# Geniric_220VAC_24VDC_cup_wash.net
KiCad netlist of a schematic drawn in EAGLE
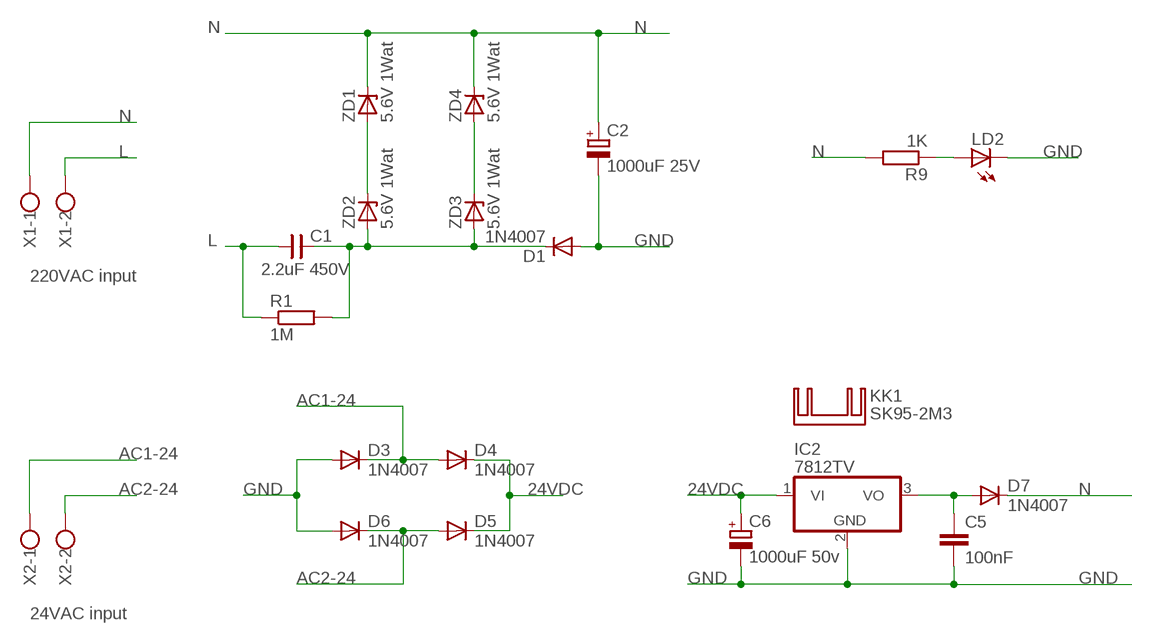
[diagram p0: schematic, sheet 1]
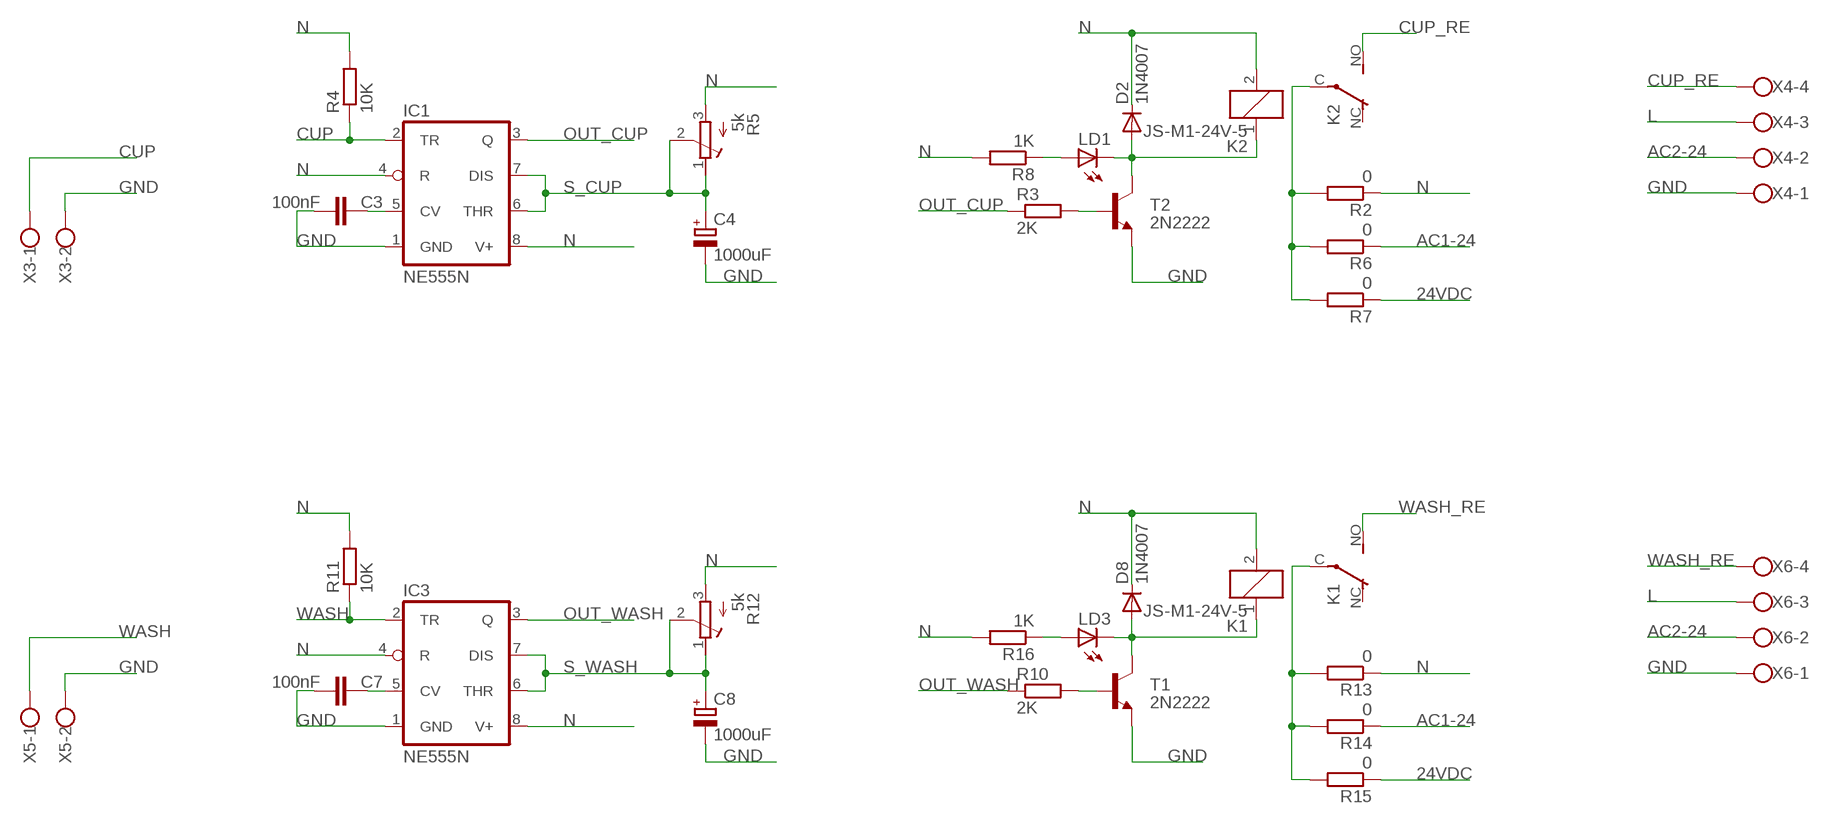
[diagram p1: schematic, sheet 2]

(export (version "E")
  (design (tool "Eeschema 10.0.6"))
  (components
    (comp (ref "C1")
      (value "2.2uF 450V")
      (footprint "eagle-import:C150-190X070")
      (libsource (lib "eagle-import") (part "CNP-C150-190X070"))
    )
    (comp (ref "C2")
      (value "1000uF 25V")
      (footprint "eagle-import:E5-8,5")
      (libsource (lib "eagle-import") (part "CPOL-EUE5-8.5"))
    )
    (comp (ref "C5")
      (value "100nF")
      (footprint "eagle-import:C050-025X075")
      (libsource (lib "eagle-import") (part "C-EU050-025X075"))
    )
    (comp (ref "C6")
      (value "1000uF 50v")
      (footprint "eagle-import:E5-13")
      (libsource (lib "eagle-import") (part "CPOL-EUE5-13"))
    )
    (comp (ref "D1")
      (value "1N4007")
      (footprint "eagle-import:DO41-10")
      (libsource (lib "eagle-import") (part "1N4004"))
    )
    (comp (ref "D3")
      (value "1N4007")
      (footprint "eagle-import:DO41-10")
      (libsource (lib "eagle-import") (part "adafruit_420_1N4004"))
    )
    (comp (ref "D4")
      (value "1N4007")
      (footprint "eagle-import:DO41-10")
      (libsource (lib "eagle-import") (part "adafruit_420_1N4004"))
    )
    (comp (ref "D5")
      (value "1N4007")
      (footprint "eagle-import:DO41-10")
      (libsource (lib "eagle-import") (part "adafruit_420_1N4004"))
    )
    (comp (ref "D6")
      (value "1N4007")
      (footprint "eagle-import:DO41-10")
      (libsource (lib "eagle-import") (part "adafruit_420_1N4004"))
    )
    (comp (ref "D7")
      (value "1N4007")
      (footprint "eagle-import:DO41-10")
      (libsource (lib "eagle-import") (part "adafruit_420_1N4004"))
    )
    (comp (ref "IC2")
      (value "7812TV")
      (footprint "eagle-import:TO220V")
      (libsource (lib "eagle-import") (part "78TV12"))
    )
    (comp (ref "KK1")
      (value "SK95-2M3")
      (footprint "eagle-import:SK95-2M3")
      (libsource (lib "eagle-import") (part "SK95-2M3"))
    )
    (comp (ref "LD2")
      (value "LED5MM")
      (footprint "eagle-import:LED5MM")
      (libsource (lib "eagle-import") (part "LED5MM"))
    )
    (comp (ref "R1")
      (value "1M")
      (footprint "eagle-import:0207_10")
      (libsource (lib "eagle-import") (part "rcl_334_R-EU_0207/10"))
    )
    (comp (ref "R9")
      (value "1K")
      (footprint "eagle-import:0207_10")
      (libsource (lib "eagle-import") (part "R-EU_0207/10"))
    )
    (comp (ref "X1")
      (value "W237-102")
      (footprint "eagle-import:W237-102")
      (libsource (lib "eagle-import") (part "W237-102"))
    )
    (comp (ref "X2")
      (value "W237-102")
      (footprint "eagle-import:W237-102")
      (libsource (lib "eagle-import") (part "W237-102"))
    )
    (comp (ref "ZD1")
      (value "5.6V 1Wat")
      (footprint "eagle-import:DO35Z10")
      (libsource (lib "eagle-import") (part "ZD-DO35Z10"))
    )
    (comp (ref "ZD2")
      (value "5.6V 1Wat")
      (footprint "eagle-import:DO35Z10")
      (libsource (lib "eagle-import") (part "ZD-DO35Z10"))
    )
    (comp (ref "ZD3")
      (value "5.6V 1Wat")
      (footprint "eagle-import:DO35Z10")
      (libsource (lib "eagle-import") (part "ZD-DO35Z10"))
    )
    (comp (ref "ZD4")
      (value "5.6V 1Wat")
      (footprint "eagle-import:DO35Z10")
      (libsource (lib "eagle-import") (part "ZD-DO35Z10"))
    )
    (comp (ref "C3")
      (value "100nF")
      (footprint "eagle-import:C050-025X075")
      (libsource (lib "eagle-import") (part "C-EU050-025X075"))
    )
    (comp (ref "C4")
      (value "1000uF")
      (footprint "eagle-import:E5-8,5")
      (libsource (lib "eagle-import") (part "CPOL-EUE5-8.5"))
    )
    (comp (ref "C7")
      (value "100nF")
      (footprint "eagle-import:C050-025X075")
      (libsource (lib "eagle-import") (part "C-EU050-025X075"))
    )
    (comp (ref "C8")
      (value "1000uF")
      (footprint "eagle-import:E5-8,5")
      (libsource (lib "eagle-import") (part "CPOL-EUE5-8.5"))
    )
    (comp (ref "D2")
      (value "1N4007")
      (footprint "eagle-import:DO41-10")
      (libsource (lib "eagle-import") (part "1N4004"))
    )
    (comp (ref "D8")
      (value "1N4007")
      (footprint "eagle-import:DO41-10")
      (libsource (lib "eagle-import") (part "1N4004"))
    )
    (comp (ref "IC1")
      (value "NE555N")
      (footprint "eagle-import:DIL08-ROUND")
      (libsource (lib "eagle-import") (part "555NNE"))
    )
    (comp (ref "IC3")
      (value "NE555N")
      (footprint "eagle-import:DIL08-ROUND")
      (libsource (lib "eagle-import") (part "555NNE"))
    )
    (comp (ref "K1")
      (value "JS-M1-24V-5")
      (footprint "eagle-import:JS-M")
      (fields (field (name "MF") "FARNELL") (field (name "MPN") "JSM1-12V-5"))
      (libsource (lib "eagle-import") (part "JS-M1-12V-5"))
    )
    (comp (ref "K2")
      (value "JS-M1-24V-5")
      (footprint "eagle-import:JS-M")
      (fields (field (name "MF") "FARNELL") (field (name "MPN") "JSM1-12V-5"))
      (libsource (lib "eagle-import") (part "JS-M1-12V-5"))
    )
    (comp (ref "LD1")
      (value "LED5MM")
      (footprint "eagle-import:LED5MM")
      (libsource (lib "eagle-import") (part "LED5MM"))
    )
    (comp (ref "LD3")
      (value "LED5MM")
      (footprint "eagle-import:LED5MM")
      (libsource (lib "eagle-import") (part "LED5MM"))
    )
    (comp (ref "R2")
      (value "0")
      (footprint "eagle-import:0207_10")
      (libsource (lib "eagle-import") (part "R-EU_0207/10"))
    )
    (comp (ref "R3")
      (value "2K")
      (footprint "eagle-import:0207_10")
      (libsource (lib "eagle-import") (part "R-EU_0207/10"))
    )
    (comp (ref "R4")
      (value "10K")
      (footprint "eagle-import:0207_10")
      (libsource (lib "eagle-import") (part "R-EU_0207/10"))
    )
    (comp (ref "R5")
      (value "5k")
      (footprint "eagle-import:RTRIMT93XA")
      (libsource (lib "eagle-import") (part "R-TRIMMT93XA"))
    )
    (comp (ref "R6")
      (value "0")
      (footprint "eagle-import:0207_10")
      (libsource (lib "eagle-import") (part "R-EU_0207/10"))
    )
    (comp (ref "R7")
      (value "0")
      (footprint "eagle-import:0207_10")
      (libsource (lib "eagle-import") (part "R-EU_0207/10"))
    )
    (comp (ref "R8")
      (value "1K")
      (footprint "eagle-import:0207_10")
      (libsource (lib "eagle-import") (part "R-EU_0207/10"))
    )
    (comp (ref "R10")
      (value "2K")
      (footprint "eagle-import:0207_10")
      (libsource (lib "eagle-import") (part "R-EU_0207/10"))
    )
    (comp (ref "R11")
      (value "10K")
      (footprint "eagle-import:0207_10")
      (libsource (lib "eagle-import") (part "R-EU_0207/10"))
    )
    (comp (ref "R12")
      (value "5k")
      (footprint "eagle-import:RTRIMT93XA")
      (libsource (lib "eagle-import") (part "R-TRIMMT93XA"))
    )
    (comp (ref "R13")
      (value "0")
      (footprint "eagle-import:0207_10")
      (libsource (lib "eagle-import") (part "R-EU_0207/10"))
    )
    (comp (ref "R14")
      (value "0")
      (footprint "eagle-import:0207_10")
      (libsource (lib "eagle-import") (part "R-EU_0207/10"))
    )
    (comp (ref "R15")
      (value "0")
      (footprint "eagle-import:0207_10")
      (libsource (lib "eagle-import") (part "R-EU_0207/10"))
    )
    (comp (ref "R16")
      (value "1K")
      (footprint "eagle-import:0207_10")
      (libsource (lib "eagle-import") (part "R-EU_0207/10"))
    )
    (comp (ref "T1")
      (value "2N2222")
      (footprint "eagle-import:TO92-EBC-OVAL")
      (libsource (lib "eagle-import") (part "2N2222"))
    )
    (comp (ref "T2")
      (value "2N2222")
      (footprint "eagle-import:TO92-EBC-OVAL")
      (libsource (lib "eagle-import") (part "2N2222"))
    )
    (comp (ref "X3")
      (value "W237-102")
      (footprint "eagle-import:W237-102")
      (libsource (lib "eagle-import") (part "W237-102"))
    )
    (comp (ref "X4")
      (value "W237-4")
      (footprint "eagle-import:W237-4")
      (libsource (lib "eagle-import") (part "W237-4"))
    )
    (comp (ref "X5")
      (value "W237-102")
      (footprint "eagle-import:W237-102")
      (libsource (lib "eagle-import") (part "W237-102"))
    )
    (comp (ref "X6")
      (value "W237-4")
      (footprint "eagle-import:W237-4")
      (libsource (lib "eagle-import") (part "W237-4"))
    )
  )
  (nets
    (net (code "1") (name "24VDC") (class "Default")
      (node (ref "C6") (pin "+") (pinfunction "+_+") (pintype "passive"))
      (node (ref "D4") (pin "C") (pinfunction "C_C") (pintype "passive"))
      (node (ref "D5") (pin "C") (pinfunction "C_C") (pintype "passive"))
      (node (ref "IC2") (pin "1") (pinfunction "VI_1") (pintype "input"))
      (node (ref "R15") (pin "1") (pinfunction "1_1") (pintype "passive"))
      (node (ref "R7") (pin "1") (pinfunction "1_1") (pintype "passive"))
    )
    (net (code "2") (name "AC1-24") (class "Default")
      (node (ref "D3") (pin "C") (pinfunction "C_C") (pintype "passive"))
      (node (ref "D4") (pin "A") (pinfunction "A_A") (pintype "passive"))
      (node (ref "R14") (pin "1") (pinfunction "1_1") (pintype "passive"))
      (node (ref "R6") (pin "1") (pinfunction "1_1") (pintype "passive"))
      (node (ref "X2") (pin "1") (pinfunction "KL_1") (pintype "passive"))
    )
    (net (code "3") (name "AC2-24") (class "Default")
      (node (ref "D5") (pin "A") (pinfunction "A_A") (pintype "passive"))
      (node (ref "D6") (pin "C") (pinfunction "C_C") (pintype "passive"))
      (node (ref "X2") (pin "2") (pinfunction "KL_2") (pintype "passive"))
      (node (ref "X4") (pin "2") (pinfunction "KL_2") (pintype "passive"))
      (node (ref "X6") (pin "2") (pinfunction "KL_2") (pintype "passive"))
    )
    (net (code "4") (name "CUP") (class "Default")
      (node (ref "IC1") (pin "2") (pinfunction "TR_2") (pintype "input"))
      (node (ref "R4") (pin "1") (pinfunction "1_1") (pintype "passive"))
      (node (ref "X3") (pin "1") (pinfunction "KL_1") (pintype "passive"))
    )
    (net (code "5") (name "CUP_RE") (class "Default")
      (node (ref "K2") (pin "NO") (pinfunction "S_NO") (pintype "passive"))
      (node (ref "X4") (pin "4") (pinfunction "KL_4") (pintype "passive"))
    )
    (net (code "6") (name "GND") (class "Default")
      (node (ref "C2") (pin "-") (pinfunction "-_-") (pintype "passive"))
      (node (ref "C3") (pin "2") (pinfunction "2_2") (pintype "passive"))
      (node (ref "C4") (pin "-") (pinfunction "-_-") (pintype "passive"))
      (node (ref "C5") (pin "2") (pinfunction "2_2") (pintype "passive"))
      (node (ref "C6") (pin "-") (pinfunction "-_-") (pintype "passive"))
      (node (ref "C7") (pin "2") (pinfunction "2_2") (pintype "passive"))
      (node (ref "C8") (pin "-") (pinfunction "-_-") (pintype "passive"))
      (node (ref "D1") (pin "A") (pinfunction "A_A") (pintype "passive"))
      (node (ref "D3") (pin "A") (pinfunction "A_A") (pintype "passive"))
      (node (ref "D6") (pin "A") (pinfunction "A_A") (pintype "passive"))
      (node (ref "IC1") (pin "1") (pinfunction "GND_1") (pintype "power_in"))
      (node (ref "IC2") (pin "2") (pinfunction "GND_2") (pintype "passive"))
      (node (ref "IC3") (pin "1") (pinfunction "GND_1") (pintype "power_in"))
      (node (ref "LD2") (pin "K") (pinfunction "C_K") (pintype "passive"))
      (node (ref "T1") (pin "E") (pinfunction "E_E") (pintype "passive"))
      (node (ref "T2") (pin "E") (pinfunction "E_E") (pintype "passive"))
      (node (ref "X3") (pin "2") (pinfunction "KL_2") (pintype "passive"))
      (node (ref "X4") (pin "1") (pinfunction "KL_1") (pintype "passive"))
      (node (ref "X5") (pin "2") (pinfunction "KL_2") (pintype "passive"))
      (node (ref "X6") (pin "1") (pinfunction "KL_1") (pintype "passive"))
    )
    (net (code "7") (name "L") (class "Default")
      (node (ref "C1") (pin "1") (pinfunction "1_1") (pintype "passive"))
      (node (ref "R1") (pin "1") (pinfunction "1_1") (pintype "passive"))
      (node (ref "X1") (pin "2") (pinfunction "KL_2") (pintype "passive"))
      (node (ref "X4") (pin "3") (pinfunction "KL_3") (pintype "passive"))
      (node (ref "X6") (pin "3") (pinfunction "KL_3") (pintype "passive"))
    )
    (net (code "8") (name "N") (class "Default")
      (node (ref "C2") (pin "+") (pinfunction "+_+") (pintype "passive"))
      (node (ref "D2") (pin "C") (pinfunction "C_C") (pintype "passive"))
      (node (ref "D7") (pin "C") (pinfunction "C_C") (pintype "passive"))
      (node (ref "D8") (pin "C") (pinfunction "C_C") (pintype "passive"))
      (node (ref "IC1") (pin "4") (pinfunction "R_4") (pintype "input"))
      (node (ref "IC1") (pin "8") (pinfunction "V+_8") (pintype "power_in"))
      (node (ref "IC3") (pin "4") (pinfunction "R_4") (pintype "input"))
      (node (ref "IC3") (pin "8") (pinfunction "V+_8") (pintype "power_in"))
      (node (ref "K1") (pin "2") (pinfunction "2_2") (pintype "passive"))
      (node (ref "K2") (pin "2") (pinfunction "2_2") (pintype "passive"))
      (node (ref "R11") (pin "2") (pinfunction "2_2") (pintype "passive"))
      (node (ref "R12") (pin "3") (pinfunction "A_3") (pintype "passive"))
      (node (ref "R13") (pin "1") (pinfunction "1_1") (pintype "passive"))
      (node (ref "R16") (pin "2") (pinfunction "2_2") (pintype "passive"))
      (node (ref "R2") (pin "1") (pinfunction "1_1") (pintype "passive"))
      (node (ref "R4") (pin "2") (pinfunction "2_2") (pintype "passive"))
      (node (ref "R5") (pin "3") (pinfunction "A_3") (pintype "passive"))
      (node (ref "R8") (pin "2") (pinfunction "2_2") (pintype "passive"))
      (node (ref "R9") (pin "2") (pinfunction "2_2") (pintype "passive"))
      (node (ref "X1") (pin "1") (pinfunction "KL_1") (pintype "passive"))
      (node (ref "ZD1") (pin "C") (pinfunction "C_C") (pintype "passive"))
      (node (ref "ZD4") (pin "C") (pinfunction "C_C") (pintype "passive"))
    )
    (net (code "9") (name "Net-(C1-Pad2)") (class "Default")
      (node (ref "C1") (pin "2") (pinfunction "2_2") (pintype "passive"))
      (node (ref "D1") (pin "C") (pinfunction "C_C") (pintype "passive"))
      (node (ref "R1") (pin "2") (pinfunction "2_2") (pintype "passive"))
      (node (ref "ZD2") (pin "A") (pinfunction "A_A") (pintype "passive"))
      (node (ref "ZD3") (pin "A") (pinfunction "A_A") (pintype "passive"))
    )
    (net (code "10") (name "Net-(IC1-CV)") (class "Default")
      (node (ref "C3") (pin "1") (pinfunction "1_1") (pintype "passive"))
      (node (ref "IC1") (pin "5") (pinfunction "CV_5") (pintype "input"))
    )
    (net (code "11") (name "Net-(IC2-VO)") (class "Default")
      (node (ref "C5") (pin "1") (pinfunction "1_1") (pintype "passive"))
      (node (ref "D7") (pin "A") (pinfunction "A_A") (pintype "passive"))
      (node (ref "IC2") (pin "3") (pinfunction "VO_3") (pintype "passive"))
    )
    (net (code "12") (name "Net-(IC3-CV)") (class "Default")
      (node (ref "C7") (pin "1") (pinfunction "1_1") (pintype "passive"))
      (node (ref "IC3") (pin "5") (pinfunction "CV_5") (pintype "input"))
    )
    (net (code "13") (name "Net-(K1B-P)") (class "Default")
      (node (ref "K1") (pin "C") (pinfunction "P_C") (pintype "passive"))
      (node (ref "R13") (pin "2") (pinfunction "2_2") (pintype "passive"))
      (node (ref "R14") (pin "2") (pinfunction "2_2") (pintype "passive"))
      (node (ref "R15") (pin "2") (pinfunction "2_2") (pintype "passive"))
    )
    (net (code "14") (name "Net-(K2B-P)") (class "Default")
      (node (ref "K2") (pin "C") (pinfunction "P_C") (pintype "passive"))
      (node (ref "R2") (pin "2") (pinfunction "2_2") (pintype "passive"))
      (node (ref "R6") (pin "2") (pinfunction "2_2") (pintype "passive"))
      (node (ref "R7") (pin "2") (pinfunction "2_2") (pintype "passive"))
    )
    (net (code "15") (name "Net-(LD1-C)") (class "Default")
      (node (ref "D2") (pin "A") (pinfunction "A_A") (pintype "passive"))
      (node (ref "K2") (pin "1") (pinfunction "1_1") (pintype "passive"))
      (node (ref "LD1") (pin "K") (pinfunction "C_K") (pintype "passive"))
      (node (ref "T2") (pin "C") (pinfunction "C_C") (pintype "passive"))
    )
    (net (code "16") (name "Net-(LD1-PadA)") (class "Default")
      (node (ref "LD1") (pin "A") (pinfunction "A_A") (pintype "passive"))
      (node (ref "R8") (pin "1") (pinfunction "1_1") (pintype "passive"))
    )
    (net (code "17") (name "Net-(LD2-PadA)") (class "Default")
      (node (ref "LD2") (pin "A") (pinfunction "A_A") (pintype "passive"))
      (node (ref "R9") (pin "1") (pinfunction "1_1") (pintype "passive"))
    )
    (net (code "18") (name "Net-(LD3-C)") (class "Default")
      (node (ref "D8") (pin "A") (pinfunction "A_A") (pintype "passive"))
      (node (ref "K1") (pin "1") (pinfunction "1_1") (pintype "passive"))
      (node (ref "LD3") (pin "K") (pinfunction "C_K") (pintype "passive"))
      (node (ref "T1") (pin "C") (pinfunction "C_C") (pintype "passive"))
    )
    (net (code "19") (name "Net-(LD3-PadA)") (class "Default")
      (node (ref "LD3") (pin "A") (pinfunction "A_A") (pintype "passive"))
      (node (ref "R16") (pin "1") (pinfunction "1_1") (pintype "passive"))
    )
    (net (code "20") (name "Net-(R3-Pad2)") (class "Default")
      (node (ref "R3") (pin "2") (pinfunction "2_2") (pintype "passive"))
      (node (ref "T2") (pin "B") (pinfunction "B_B") (pintype "passive"))
    )
    (net (code "21") (name "Net-(R10-Pad2)") (class "Default")
      (node (ref "R10") (pin "2") (pinfunction "2_2") (pintype "passive"))
      (node (ref "T1") (pin "B") (pinfunction "B_B") (pintype "passive"))
    )
    (net (code "22") (name "Net-(ZD1-PadA)") (class "Default")
      (node (ref "ZD1") (pin "A") (pinfunction "A_A") (pintype "passive"))
      (node (ref "ZD2") (pin "C") (pinfunction "C_C") (pintype "passive"))
    )
    (net (code "23") (name "Net-(ZD3-PadC)") (class "Default")
      (node (ref "ZD3") (pin "C") (pinfunction "C_C") (pintype "passive"))
      (node (ref "ZD4") (pin "A") (pinfunction "A_A") (pintype "passive"))
    )
    (net (code "24") (name "OUT_CUP") (class "Default")
      (node (ref "IC1") (pin "3") (pinfunction "Q_3") (pintype "output"))
      (node (ref "R3") (pin "1") (pinfunction "1_1") (pintype "passive"))
    )
    (net (code "25") (name "OUT_WASH") (class "Default")
      (node (ref "IC3") (pin "3") (pinfunction "Q_3") (pintype "output"))
      (node (ref "R10") (pin "1") (pinfunction "1_1") (pintype "passive"))
    )
    (net (code "26") (name "S_CUP") (class "Default")
      (node (ref "C4") (pin "+") (pinfunction "+_+") (pintype "passive"))
      (node (ref "IC1") (pin "6") (pinfunction "THR_6") (pintype "input"))
      (node (ref "IC1") (pin "7") (pinfunction "DIS_7") (pintype "input"))
      (node (ref "R5") (pin "1") (pinfunction "E_1") (pintype "passive"))
      (node (ref "R5") (pin "2") (pinfunction "S_2") (pintype "passive"))
    )
    (net (code "27") (name "S_WASH") (class "Default")
      (node (ref "C8") (pin "+") (pinfunction "+_+") (pintype "passive"))
      (node (ref "IC3") (pin "6") (pinfunction "THR_6") (pintype "input"))
      (node (ref "IC3") (pin "7") (pinfunction "DIS_7") (pintype "input"))
      (node (ref "R12") (pin "1") (pinfunction "E_1") (pintype "passive"))
      (node (ref "R12") (pin "2") (pinfunction "S_2") (pintype "passive"))
    )
    (net (code "28") (name "WASH") (class "Default")
      (node (ref "IC3") (pin "2") (pinfunction "TR_2") (pintype "input"))
      (node (ref "R11") (pin "1") (pinfunction "1_1") (pintype "passive"))
      (node (ref "X5") (pin "1") (pinfunction "KL_1") (pintype "passive"))
    )
    (net (code "29") (name "WASH_RE") (class "Default")
      (node (ref "K1") (pin "NO") (pinfunction "S_NO") (pintype "passive"))
      (node (ref "X6") (pin "4") (pinfunction "KL_4") (pintype "passive"))
    )
    (net (code "30") (name "unconnected-(K1B-O-PadNC)") (class "Default")
      (node (ref "K1") (pin "NC") (pinfunction "O_NC") (pintype "passive"))
    )
    (net (code "31") (name "unconnected-(K2B-O-PadNC)") (class "Default")
      (node (ref "K2") (pin "NC") (pinfunction "O_NC") (pintype "passive"))
    )
  )
)
